# ESP32_SRAM.net
KiCad netlist of a schematic drawn in Altium Designer
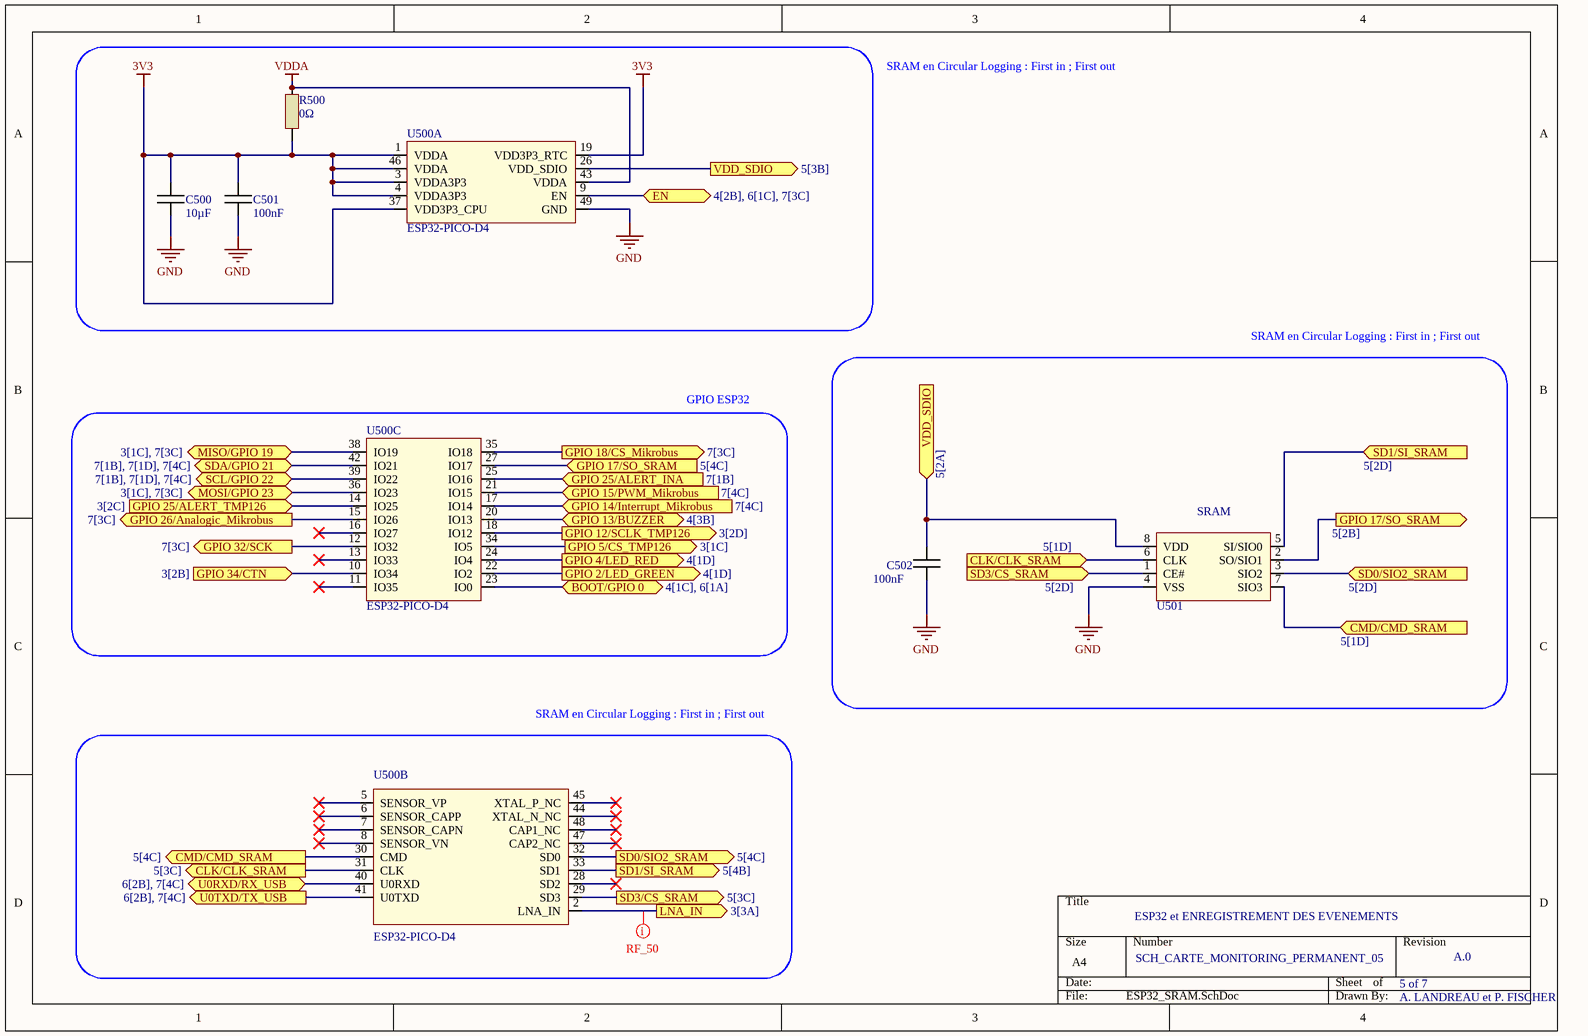
[diagram p0: ESP32_SRAM.SchDoc]

(export (version "E")
  (design (tool "Eeschema 10.0.6"))
  (components
    (comp (ref "C500")
      (value "10µF")
      (footprint "CAPC1005X06N")
      (libsource (lib "SCHLibrary") (part "Capacitor"))
    )
    (comp (ref "C501")
      (value "100nF")
      (footprint "CAPC1005X06N")
      (libsource (lib "SCHLibrary") (part "Capacitor"))
    )
    (comp (ref "C502")
      (value "100nF")
      (footprint "CAPC1005X06N")
      (libsource (lib "SCHLibrary") (part "Capacitor"))
    )
    (comp (ref "R500")
      (value "0Ω")
      (footprint "RESC1005X06N")
      (libsource (lib "SCHLibrary") (part "Resistor"))
    )
    (comp (ref "U500")
      (value "ESP32-PICO-D4")
      (footprint "PQFN50P700X700X104_HS-49N")
      (libsource (lib "SCHLibrary") (part "ESP32"))
    )
    (comp (ref "U501")
      (value "IS66WVS1M8BLL-104NLI")
      (footprint "SOIC127P600X175-8N")
      (description "SRAM 8Mb, SerialRAM, 2.7V-3.6V, 104MHz, 8 pin SOIC 150 mil, RoHS")
      (libsource (lib "SCHLibrary") (part "SRAM"))
    )
  )
  (nets
    (net (code "1") (name "/BOOT{slash}GPIO 0") (class "Default")
      (node (ref "U500") (pin "23") (pinfunction "IO0_23") (pintype "passive"))
    )
    (net (code "2") (name "/CLK{slash}CLK_SRAM") (class "Default")
      (node (ref "U500") (pin "31") (pinfunction "CLK_31") (pintype "passive"))
      (node (ref "U501") (pin "6") (pinfunction "CLK_6") (pintype "passive"))
    )
    (net (code "3") (name "/CMD{slash}CMD_SRAM") (class "Default")
      (node (ref "U500") (pin "30") (pinfunction "CMD_30") (pintype "passive"))
      (node (ref "U501") (pin "7") (pinfunction "SIO3_7") (pintype "passive"))
    )
    (net (code "4") (name "/EN") (class "Default")
      (node (ref "U500") (pin "9") (pinfunction "EN_9") (pintype "passive"))
    )
    (net (code "5") (name "/GPIO 2{slash}LED_GREEN") (class "Default")
      (node (ref "U500") (pin "22") (pinfunction "IO2_22") (pintype "passive"))
    )
    (net (code "6") (name "/GPIO 4{slash}LED_RED") (class "Default")
      (node (ref "U500") (pin "24") (pinfunction "IO4_24") (pintype "passive"))
    )
    (net (code "7") (name "/GPIO 5{slash}CS_TMP126") (class "Default")
      (node (ref "U500") (pin "34") (pinfunction "IO5_34") (pintype "passive"))
    )
    (net (code "8") (name "/GPIO 12{slash}SCLK_TMP126") (class "Default")
      (node (ref "U500") (pin "18") (pinfunction "IO12_18") (pintype "passive"))
    )
    (net (code "9") (name "/GPIO 13{slash}BUZZER") (class "Default")
      (node (ref "U500") (pin "20") (pinfunction "IO13_20") (pintype "passive"))
    )
    (net (code "10") (name "/GPIO 14{slash}Interrupt_Mikrobus") (class "Default")
      (node (ref "U500") (pin "17") (pinfunction "IO14_17") (pintype "passive"))
    )
    (net (code "11") (name "/GPIO 15{slash}PWM_Mikrobus") (class "Default")
      (node (ref "U500") (pin "21") (pinfunction "IO15_21") (pintype "passive"))
    )
    (net (code "12") (name "/GPIO 17{slash}SO_SRAM") (class "Default")
      (node (ref "U500") (pin "27") (pinfunction "IO17_27") (pintype "passive"))
      (node (ref "U501") (pin "2") (pinfunction "SO/SIO1_2") (pintype "passive"))
    )
    (net (code "13") (name "/GPIO 18{slash}CS_Mikrobus") (class "Default")
      (node (ref "U500") (pin "35") (pinfunction "IO18_35") (pintype "passive"))
    )
    (net (code "14") (name "/GPIO 25{slash}ALERT_INA") (class "Default")
      (node (ref "U500") (pin "25") (pinfunction "IO16_25") (pintype "passive"))
    )
    (net (code "15") (name "/GPIO 25{slash}ALERT_TMP126") (class "Default")
      (node (ref "U500") (pin "14") (pinfunction "IO25_14") (pintype "passive"))
    )
    (net (code "16") (name "/GPIO 26{slash}Analogic_Mikrobus") (class "Default")
      (node (ref "U500") (pin "15") (pinfunction "IO26_15") (pintype "passive"))
    )
    (net (code "17") (name "/GPIO 32{slash}SCK") (class "Default")
      (node (ref "U500") (pin "12") (pinfunction "IO32_12") (pintype "passive"))
    )
    (net (code "18") (name "/GPIO 34{slash}CTN") (class "Default")
      (node (ref "U500") (pin "10") (pinfunction "IO34_10") (pintype "passive"))
    )
    (net (code "19") (name "/LNA_IN") (class "Default")
      (node (ref "U500") (pin "2") (pinfunction "LNA_IN_2") (pintype "passive"))
    )
    (net (code "20") (name "/MISO{slash}GPIO 19") (class "Default")
      (node (ref "U500") (pin "38") (pinfunction "IO19_38") (pintype "passive"))
    )
    (net (code "21") (name "/MOSI{slash}GPIO 23") (class "Default")
      (node (ref "U500") (pin "36") (pinfunction "IO23_36") (pintype "passive"))
    )
    (net (code "22") (name "/SCL{slash}GPIO 22") (class "Default")
      (node (ref "U500") (pin "39") (pinfunction "IO22_39") (pintype "passive"))
    )
    (net (code "23") (name "/SD0{slash}SIO2_SRAM") (class "Default")
      (node (ref "U500") (pin "32") (pinfunction "SD0_32") (pintype "passive"))
      (node (ref "U501") (pin "3") (pinfunction "SIO2_3") (pintype "passive"))
    )
    (net (code "24") (name "/SD1{slash}SI_SRAM") (class "Default")
      (node (ref "U500") (pin "33") (pinfunction "SD1_33") (pintype "passive"))
      (node (ref "U501") (pin "5") (pinfunction "SI/SIO0_5") (pintype "passive"))
    )
    (net (code "25") (name "/SD3{slash}CS_SRAM") (class "Default")
      (node (ref "U500") (pin "29") (pinfunction "SD3_29") (pintype "passive"))
      (node (ref "U501") (pin "1") (pinfunction "CE#_1") (pintype "passive"))
    )
    (net (code "26") (name "/SDA{slash}GPIO 21") (class "Default")
      (node (ref "U500") (pin "42") (pinfunction "IO21_42") (pintype "passive"))
    )
    (net (code "27") (name "/U0RXD{slash}RX_USB") (class "Default")
      (node (ref "U500") (pin "40") (pinfunction "U0RXD_40") (pintype "passive"))
    )
    (net (code "28") (name "/U0TXD{slash}TX_USB") (class "Default")
      (node (ref "U500") (pin "41") (pinfunction "U0TXD_41") (pintype "passive"))
    )
    (net (code "29") (name "/VDD_SDIO") (class "Default")
      (node (ref "C502") (pin "1") (pinfunction "1_1") (pintype "passive"))
      (node (ref "U500") (pin "26") (pinfunction "VDD_SDIO_26") (pintype "passive"))
      (node (ref "U501") (pin "8") (pinfunction "VDD_8") (pintype "passive"))
    )
    (net (code "30") (name "3V3") (class "Default")
      (node (ref "C500") (pin "1") (pinfunction "1_1") (pintype "passive"))
      (node (ref "C501") (pin "1") (pinfunction "1_1") (pintype "passive"))
      (node (ref "R500") (pin "1") (pinfunction "1_1") (pintype "passive"))
      (node (ref "U500") (pin "1") (pinfunction "VDDA_1") (pintype "passive"))
      (node (ref "U500") (pin "19") (pinfunction "VDD3P3_RTC_19") (pintype "passive"))
      (node (ref "U500") (pin "3") (pinfunction "VDDA3P3_3") (pintype "passive"))
      (node (ref "U500") (pin "37") (pinfunction "VDD3P3_CPU_37") (pintype "passive"))
      (node (ref "U500") (pin "4") (pinfunction "VDDA3P3_4") (pintype "passive"))
      (node (ref "U500") (pin "46") (pinfunction "VDDA_46") (pintype "passive"))
    )
    (net (code "31") (name "GND") (class "Default")
      (node (ref "C500") (pin "2") (pinfunction "2_2") (pintype "passive"))
      (node (ref "C501") (pin "2") (pinfunction "2_2") (pintype "passive"))
      (node (ref "C502") (pin "2") (pinfunction "2_2") (pintype "passive"))
      (node (ref "U500") (pin "49") (pinfunction "GND_49") (pintype "passive"))
      (node (ref "U501") (pin "4") (pinfunction "VSS_4") (pintype "passive"))
    )
    (net (code "32") (name "VDDA") (class "Default")
      (node (ref "R500") (pin "2") (pinfunction "2_2") (pintype "passive"))
      (node (ref "U500") (pin "43") (pinfunction "VDDA_43") (pintype "passive"))
    )
    (net (code "33") (name "unconnected-(U500B-CAP1_NC-Pad48)") (class "Default")
      (node (ref "U500") (pin "48") (pinfunction "CAP1_NC_48") (pintype "passive+no_connect"))
    )
    (net (code "34") (name "unconnected-(U500B-CAP2_NC-Pad47)") (class "Default")
      (node (ref "U500") (pin "47") (pinfunction "CAP2_NC_47") (pintype "passive+no_connect"))
    )
    (net (code "35") (name "unconnected-(U500B-SD2-Pad28)") (class "Default")
      (node (ref "U500") (pin "28") (pinfunction "SD2_28") (pintype "passive+no_connect"))
    )
    (net (code "36") (name "unconnected-(U500B-SENSOR_CAPN-Pad7)") (class "Default")
      (node (ref "U500") (pin "7") (pinfunction "SENSOR_CAPN_7") (pintype "passive+no_connect"))
    )
    (net (code "37") (name "unconnected-(U500B-SENSOR_CAPP-Pad6)") (class "Default")
      (node (ref "U500") (pin "6") (pinfunction "SENSOR_CAPP_6") (pintype "passive+no_connect"))
    )
    (net (code "38") (name "unconnected-(U500B-SENSOR_VN-Pad8)") (class "Default")
      (node (ref "U500") (pin "8") (pinfunction "SENSOR_VN_8") (pintype "passive+no_connect"))
    )
    (net (code "39") (name "unconnected-(U500B-SENSOR_VP-Pad5)") (class "Default")
      (node (ref "U500") (pin "5") (pinfunction "SENSOR_VP_5") (pintype "passive+no_connect"))
    )
    (net (code "40") (name "unconnected-(U500B-XTAL_N_NC-Pad44)") (class "Default")
      (node (ref "U500") (pin "44") (pinfunction "XTAL_N_NC_44") (pintype "passive+no_connect"))
    )
    (net (code "41") (name "unconnected-(U500B-XTAL_P_NC-Pad45)") (class "Default")
      (node (ref "U500") (pin "45") (pinfunction "XTAL_P_NC_45") (pintype "passive+no_connect"))
    )
    (net (code "42") (name "unconnected-(U500C-IO27-Pad16)") (class "Default")
      (node (ref "U500") (pin "16") (pinfunction "IO27_16") (pintype "passive+no_connect"))
    )
    (net (code "43") (name "unconnected-(U500C-IO33-Pad13)") (class "Default")
      (node (ref "U500") (pin "13") (pinfunction "IO33_13") (pintype "passive+no_connect"))
    )
    (net (code "44") (name "unconnected-(U500C-IO35-Pad11)") (class "Default")
      (node (ref "U500") (pin "11") (pinfunction "IO35_11") (pintype "passive+no_connect"))
    )
  )
)
